# Adafruit_BH1750.net
KiCad netlist of a schematic drawn in EAGLE
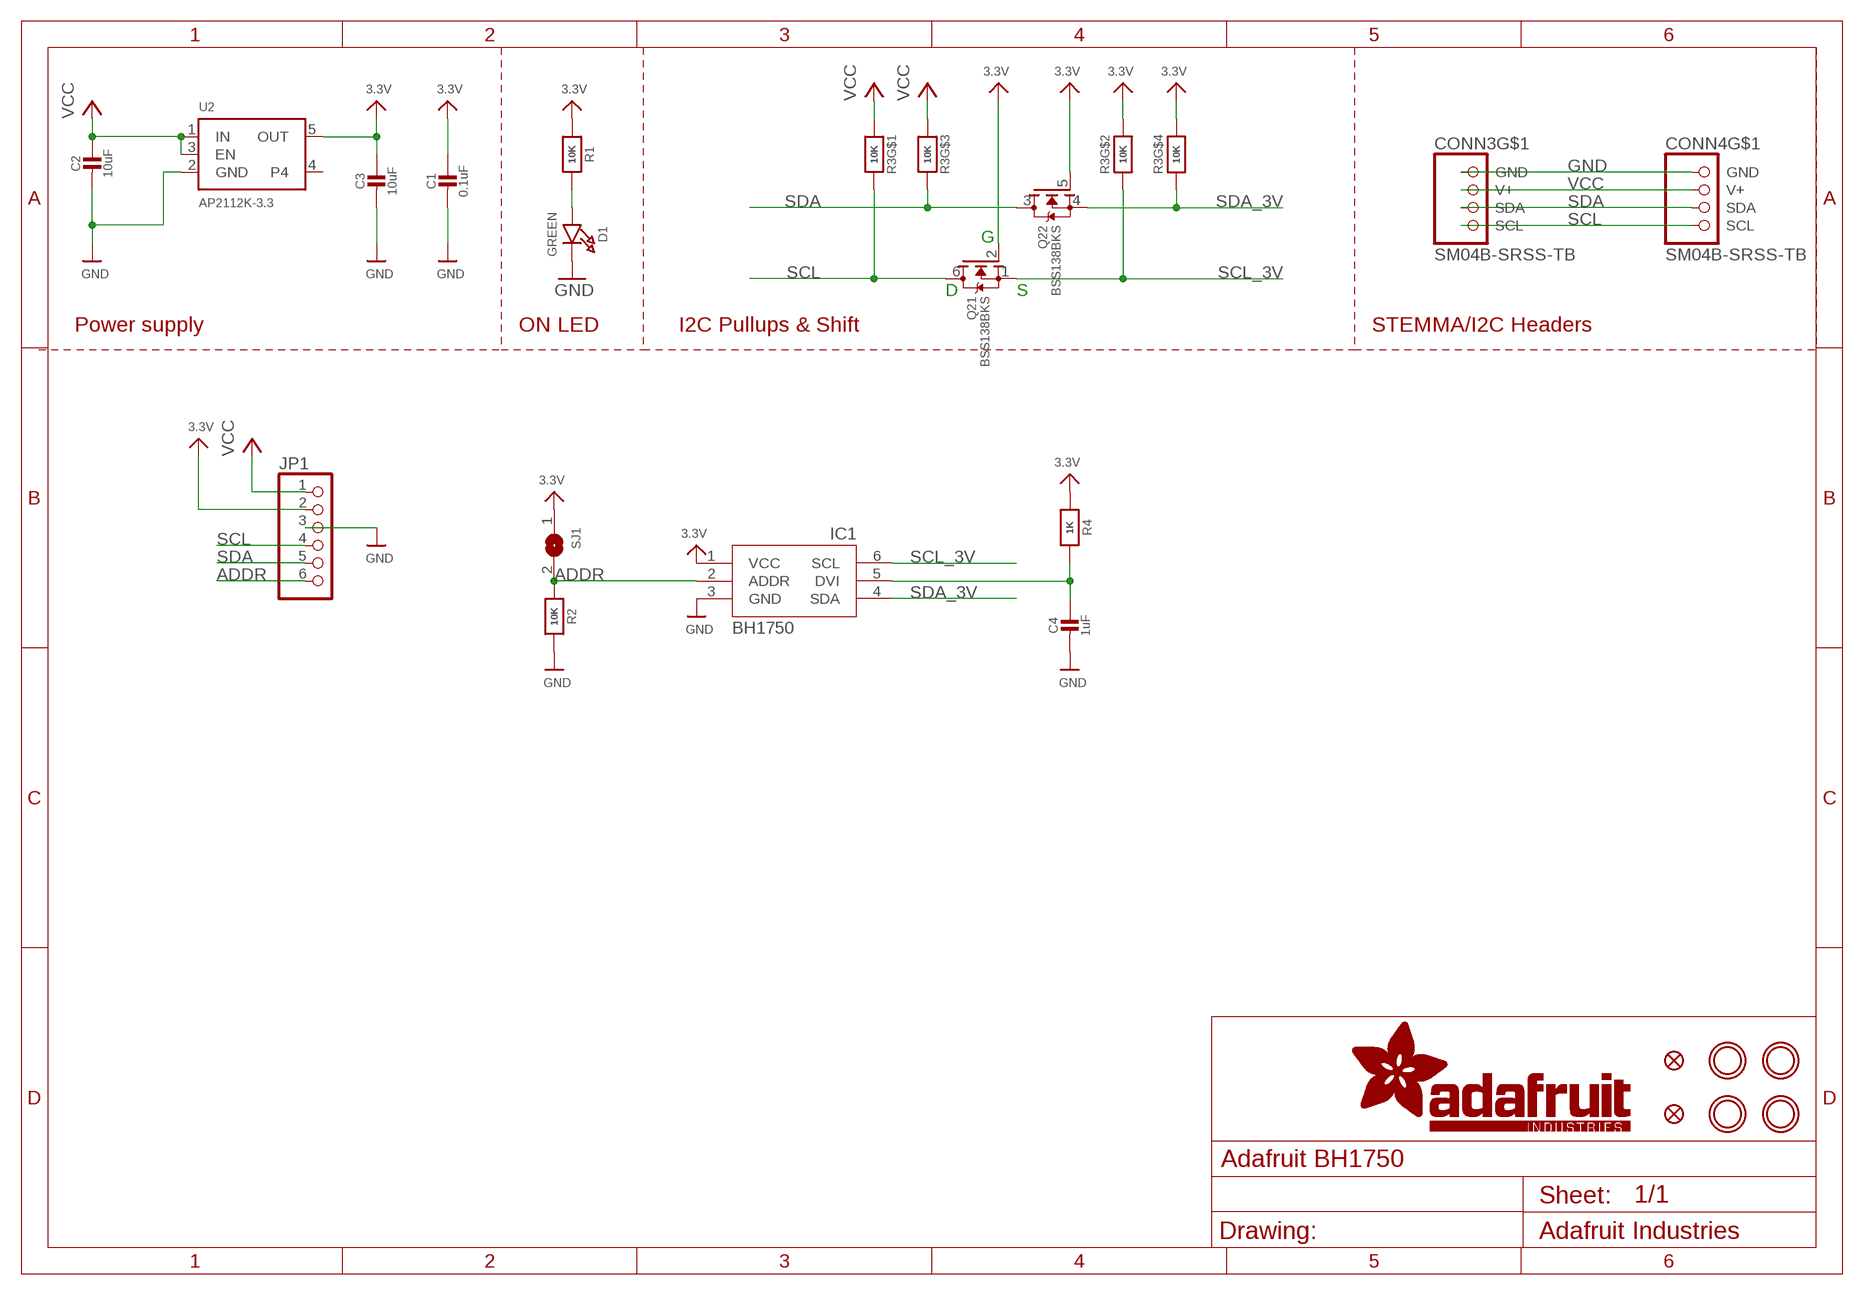
[diagram p0: schematic, sheet 1]

(export (version "E")
  (design (tool "Eeschema 10.0.6"))
  (components
    (comp (ref "C1")
      (value "0.1uF")
      (footprint "eagle-import:0603-NO")
      (libsource (lib "eagle-import") (part "CAP_CERAMIC0603_NO"))
    )
    (comp (ref "C2")
      (value "10uF")
      (footprint "eagle-import:0805-NO")
      (libsource (lib "eagle-import") (part "CAP_CERAMIC0805-NOOUTLINE"))
    )
    (comp (ref "C3")
      (value "10uF")
      (footprint "eagle-import:0805-NO")
      (libsource (lib "eagle-import") (part "CAP_CERAMIC0805-NOOUTLINE"))
    )
    (comp (ref "C4")
      (value "1uF")
      (footprint "eagle-import:0603-NO")
      (libsource (lib "eagle-import") (part "CAP_CERAMIC0603_NO"))
    )
    (comp (ref "CONN3")
      (value "SM04B-SRSS-TB")
      (footprint "eagle-import:JST_SH4")
      (libsource (lib "eagle-import") (part "STEMMA_I2C_QT"))
    )
    (comp (ref "CONN4")
      (value "SM04B-SRSS-TB")
      (footprint "eagle-import:JST_SH4")
      (libsource (lib "eagle-import") (part "STEMMA_I2C_QT"))
    )
    (comp (ref "D1")
      (value "GREEN")
      (footprint "eagle-import:CHIPLED_0603_NOOUTLINE")
      (libsource (lib "eagle-import") (part "LED0603_NOOUTLINE"))
    )
    (comp (ref "FID3")
      (value "FIDUCIAL_1MM")
      (footprint "eagle-import:FIDUCIAL_1MM")
      (libsource (lib "eagle-import") (part "FIDUCIAL_1MM"))
    )
    (comp (ref "FID4")
      (value "FIDUCIAL_1MM")
      (footprint "eagle-import:FIDUCIAL_1MM")
      (libsource (lib "eagle-import") (part "FIDUCIAL_1MM"))
    )
    (comp (ref "IC1")
      (value "BH1750")
      (footprint "eagle-import:WSOF-6")
      (libsource (lib "eagle-import") (part "BH1750"))
    )
    (comp (ref "JP1")
      (value "HEADER-1X670MIL")
      (footprint "eagle-import:1X06_ROUND_70")
      (libsource (lib "eagle-import") (part "HEADER-1X670MIL"))
    )
    (comp (ref "Q2")
      (value "BSS138BKS")
      (footprint "eagle-import:SOT363")
      (libsource (lib "eagle-import") (part "MOSFET-N_DUAL"))
    )
    (comp (ref "R1")
      (value "10K")
      (footprint "eagle-import:0603-NO")
      (libsource (lib "eagle-import") (part "RESISTOR_0603_NOOUT"))
    )
    (comp (ref "R2")
      (value "10K")
      (footprint "eagle-import:0603-NO")
      (libsource (lib "eagle-import") (part "RESISTOR_0603_NOOUT"))
    )
    (comp (ref "R3")
      (value "10K")
      (footprint "eagle-import:RESPACK_4X0603")
      (libsource (lib "eagle-import") (part "RESISTOR_4PACK"))
    )
    (comp (ref "R4")
      (value "1K")
      (footprint "eagle-import:0603-NO")
      (libsource (lib "eagle-import") (part "RESISTOR_0603_NOOUT"))
    )
    (comp (ref "SJ1")
      (value "SOLDERJUMPER")
      (footprint "eagle-import:SOLDERJUMPER_ARROW_NOPASTE")
      (libsource (lib "eagle-import") (part "SOLDERJUMPER"))
    )
    (comp (ref "U$1")
      (value "MOUNTINGHOLE2.5")
      (footprint "eagle-import:MOUNTINGHOLE_2.5_PLATED")
      (libsource (lib "eagle-import") (part "MOUNTINGHOLE2.5"))
    )
    (comp (ref "U$17")
      (value "MOUNTINGHOLE2.5")
      (footprint "eagle-import:MOUNTINGHOLE_2.5_PLATED")
      (libsource (lib "eagle-import") (part "MOUNTINGHOLE2.5"))
    )
    (comp (ref "U$19")
      (value "MOUNTINGHOLE2.5")
      (footprint "eagle-import:MOUNTINGHOLE_2.5_PLATED")
      (libsource (lib "eagle-import") (part "MOUNTINGHOLE2.5"))
    )
    (comp (ref "U$21")
      (value "MOUNTINGHOLE2.5")
      (footprint "eagle-import:MOUNTINGHOLE_2.5_PLATED")
      (libsource (lib "eagle-import") (part "MOUNTINGHOLE2.5"))
    )
    (comp (ref "U2")
      (value "AP2112K-3.3")
      (footprint "eagle-import:SOT23-5")
      (libsource (lib "eagle-import") (part "VREG_SOT23-5"))
    )
  )
  (nets
    (net (code "1") (name "/ADDR") (class "Default")
      (node (ref "IC1") (pin "2") (pinfunction "ADDR_2") (pintype "input"))
      (node (ref "JP1") (pin "6") (pinfunction "6_6") (pintype "passive"))
      (node (ref "R2") (pin "1") (pinfunction "1_1") (pintype "passive"))
      (node (ref "SJ1") (pin "2") (pinfunction "2_2") (pintype "passive"))
    )
    (net (code "2") (name "/SCL") (class "Default")
      (node (ref "CONN3") (pin "4") (pinfunction "SCL_4") (pintype "passive"))
      (node (ref "CONN4") (pin "4") (pinfunction "SCL_4") (pintype "passive"))
      (node (ref "JP1") (pin "4") (pinfunction "4_4") (pintype "passive"))
      (node (ref "Q2") (pin "6") (pinfunction "D_6") (pintype "bidirectional"))
      (node (ref "R3") (pin "8") (pinfunction "2_8") (pintype "passive"))
    )
    (net (code "3") (name "/SCL_3V") (class "Default")
      (node (ref "IC1") (pin "6") (pinfunction "SCL_6") (pintype "bidirectional"))
      (node (ref "Q2") (pin "1") (pinfunction "S_1") (pintype "bidirectional"))
      (node (ref "R3") (pin "7") (pinfunction "2_7") (pintype "passive"))
    )
    (net (code "4") (name "/SDA") (class "Default")
      (node (ref "CONN3") (pin "3") (pinfunction "SDA_3") (pintype "passive"))
      (node (ref "CONN4") (pin "3") (pinfunction "SDA_3") (pintype "passive"))
      (node (ref "JP1") (pin "5") (pinfunction "5_5") (pintype "passive"))
      (node (ref "Q2") (pin "3") (pinfunction "D_3") (pintype "bidirectional"))
      (node (ref "R3") (pin "6") (pinfunction "2_6") (pintype "passive"))
    )
    (net (code "5") (name "/SDA_3V") (class "Default")
      (node (ref "IC1") (pin "4") (pinfunction "SDA_4") (pintype "bidirectional"))
      (node (ref "Q2") (pin "4") (pinfunction "S_4") (pintype "bidirectional"))
      (node (ref "R3") (pin "5") (pinfunction "2_5") (pintype "passive"))
    )
    (net (code "6") (name "3.3V") (class "Default")
      (node (ref "C1") (pin "1") (pinfunction "1_1") (pintype "passive"))
      (node (ref "C3") (pin "1") (pinfunction "1_1") (pintype "passive"))
      (node (ref "IC1") (pin "1") (pinfunction "VCC_1") (pintype "power_in"))
      (node (ref "JP1") (pin "2") (pinfunction "2_2") (pintype "passive"))
      (node (ref "Q2") (pin "2") (pinfunction "G_2") (pintype "bidirectional"))
      (node (ref "Q2") (pin "5") (pinfunction "G_5") (pintype "bidirectional"))
      (node (ref "R1") (pin "1") (pinfunction "1_1") (pintype "passive"))
      (node (ref "R3") (pin "2") (pinfunction "1_2") (pintype "passive"))
      (node (ref "R3") (pin "4") (pinfunction "1_4") (pintype "passive"))
      (node (ref "R4") (pin "1") (pinfunction "1_1") (pintype "passive"))
      (node (ref "SJ1") (pin "1") (pinfunction "1_1") (pintype "passive"))
      (node (ref "U2") (pin "5") (pinfunction "OUT_5") (pintype "power_in"))
    )
    (net (code "7") (name "GND") (class "Default")
      (node (ref "C1") (pin "2") (pinfunction "2_2") (pintype "passive"))
      (node (ref "C2") (pin "2") (pinfunction "2_2") (pintype "passive"))
      (node (ref "C3") (pin "2") (pinfunction "2_2") (pintype "passive"))
      (node (ref "C4") (pin "2") (pinfunction "2_2") (pintype "passive"))
      (node (ref "CONN3") (pin "1") (pinfunction "GND_1") (pintype "passive"))
      (node (ref "CONN4") (pin "1") (pinfunction "GND_1") (pintype "passive"))
      (node (ref "D1") (pin "C") (pinfunction "C_C") (pintype "passive"))
      (node (ref "IC1") (pin "3") (pinfunction "GND_3") (pintype "power_in"))
      (node (ref "JP1") (pin "3") (pinfunction "3_3") (pintype "passive"))
      (node (ref "R2") (pin "2") (pinfunction "2_2") (pintype "passive"))
      (node (ref "U2") (pin "2") (pinfunction "GND_2") (pintype "power_in"))
    )
    (net (code "8") (name "Net-(D1-PadA)") (class "Default")
      (node (ref "D1") (pin "A") (pinfunction "A_A") (pintype "passive"))
      (node (ref "R1") (pin "2") (pinfunction "2_2") (pintype "passive"))
    )
    (net (code "9") (name "Net-(IC1-DVI)") (class "Default")
      (node (ref "C4") (pin "1") (pinfunction "1_1") (pintype "passive"))
      (node (ref "IC1") (pin "5") (pinfunction "DVI_5") (pintype "input"))
      (node (ref "R4") (pin "2") (pinfunction "2_2") (pintype "passive"))
    )
    (net (code "10") (name "VCC") (class "Default")
      (node (ref "C2") (pin "1") (pinfunction "1_1") (pintype "passive"))
      (node (ref "CONN3") (pin "2") (pinfunction "V+_2") (pintype "passive"))
      (node (ref "CONN4") (pin "2") (pinfunction "V+_2") (pintype "passive"))
      (node (ref "JP1") (pin "1") (pinfunction "1_1") (pintype "passive"))
      (node (ref "R3") (pin "1") (pinfunction "1_1") (pintype "passive"))
      (node (ref "R3") (pin "3") (pinfunction "1_3") (pintype "passive"))
      (node (ref "U2") (pin "1") (pinfunction "IN_1") (pintype "power_in"))
      (node (ref "U2") (pin "3") (pinfunction "EN_3") (pintype "input"))
    )
    (net (code "11") (name "unconnected-(U2-P4-Pad4)") (class "Default")
      (node (ref "U2") (pin "4") (pinfunction "P4_4") (pintype "bidirectional"))
    )
  )
)
